# LDO.net
KiCad netlist of a schematic drawn in Altium Designer
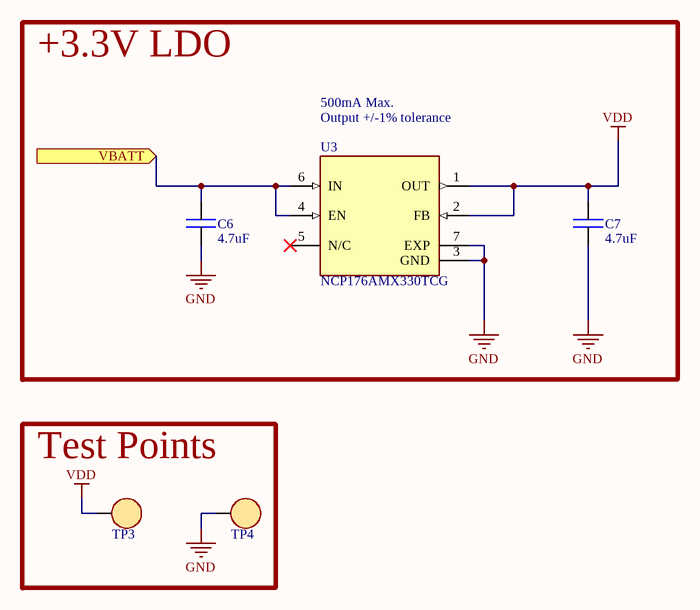
[diagram p0: LDO.SchDoc]

(export (version "E")
  (design (tool "Eeschema 10.0.6"))
  (components
    (comp (ref "C6")
      (value "4.7uF")
      (footprint "PressurePulse:0402C")
      (description "Capacitor")
      (fields (field (name "Comment") "CAP"))
      (libsource (lib "PressurePulse") (part "CAP"))
    )
    (comp (ref "C7")
      (value "4.7uF")
      (footprint "PressurePulse:0402C")
      (description "Capacitor")
      (fields (field (name "Comment") "CAP"))
      (libsource (lib "PressurePulse") (part "CAP"))
    )
    (comp (ref "TP3")
      (value "RH-5019")
      (footprint "PressurePulse:TP - RH-5019")
      (fields (field (name "MFR") "ronghe"))
      (libsource (lib "PressurePulse") (part "TEST POINT"))
    )
    (comp (ref "TP4")
      (value "RH-5019")
      (footprint "PressurePulse:TP - RH-5019")
      (fields (field (name "MFR") "ronghe"))
      (libsource (lib "PressurePulse") (part "TEST POINT"))
    )
    (comp (ref "U3")
      (value "NCP176AMX330TCG")
      (footprint "PressurePulse:6-XDFN")
      (description "LDO REGULATOR")
      (fields (field (name "MFR") "onsemi"))
      (libsource (lib "PressurePulse") (part "LDO 3.3V"))
    )
  )
  (nets
    (net (code "1") (name "/VBATT") (class "Default")
      (node (ref "C6") (pin "2") (pinfunction "2_2") (pintype "passive"))
      (node (ref "U3") (pin "4") (pinfunction "EN_4") (pintype "input"))
      (node (ref "U3") (pin "6") (pinfunction "IN_6") (pintype "input"))
    )
    (net (code "2") (name "GND") (class "Default")
      (node (ref "C6") (pin "1") (pinfunction "1_1") (pintype "passive"))
      (node (ref "C7") (pin "1") (pinfunction "1_1") (pintype "passive"))
      (node (ref "TP4") (pin "1") (pinfunction "1_1") (pintype "passive"))
      (node (ref "U3") (pin "3") (pinfunction "GND_3") (pintype "power_in"))
      (node (ref "U3") (pin "7") (pinfunction "EXP_7") (pintype "power_in"))
    )
    (net (code "3") (name "VDD") (class "Default")
      (node (ref "C7") (pin "2") (pinfunction "2_2") (pintype "passive"))
      (node (ref "TP3") (pin "1") (pinfunction "1_1") (pintype "passive"))
      (node (ref "U3") (pin "1") (pinfunction "OUT_1") (pintype "output"))
      (node (ref "U3") (pin "2") (pinfunction "FB_2") (pintype "input"))
    )
    (net (code "4") (name "unconnected-(U3-N{slash}C-Pad5)") (class "Default")
      (node (ref "U3") (pin "5") (pinfunction "N/C_5") (pintype "passive+no_connect"))
    )
  )
)
